# Schematic_EasyEDA.net
KiCad netlist of a schematic drawn in EasyEDA
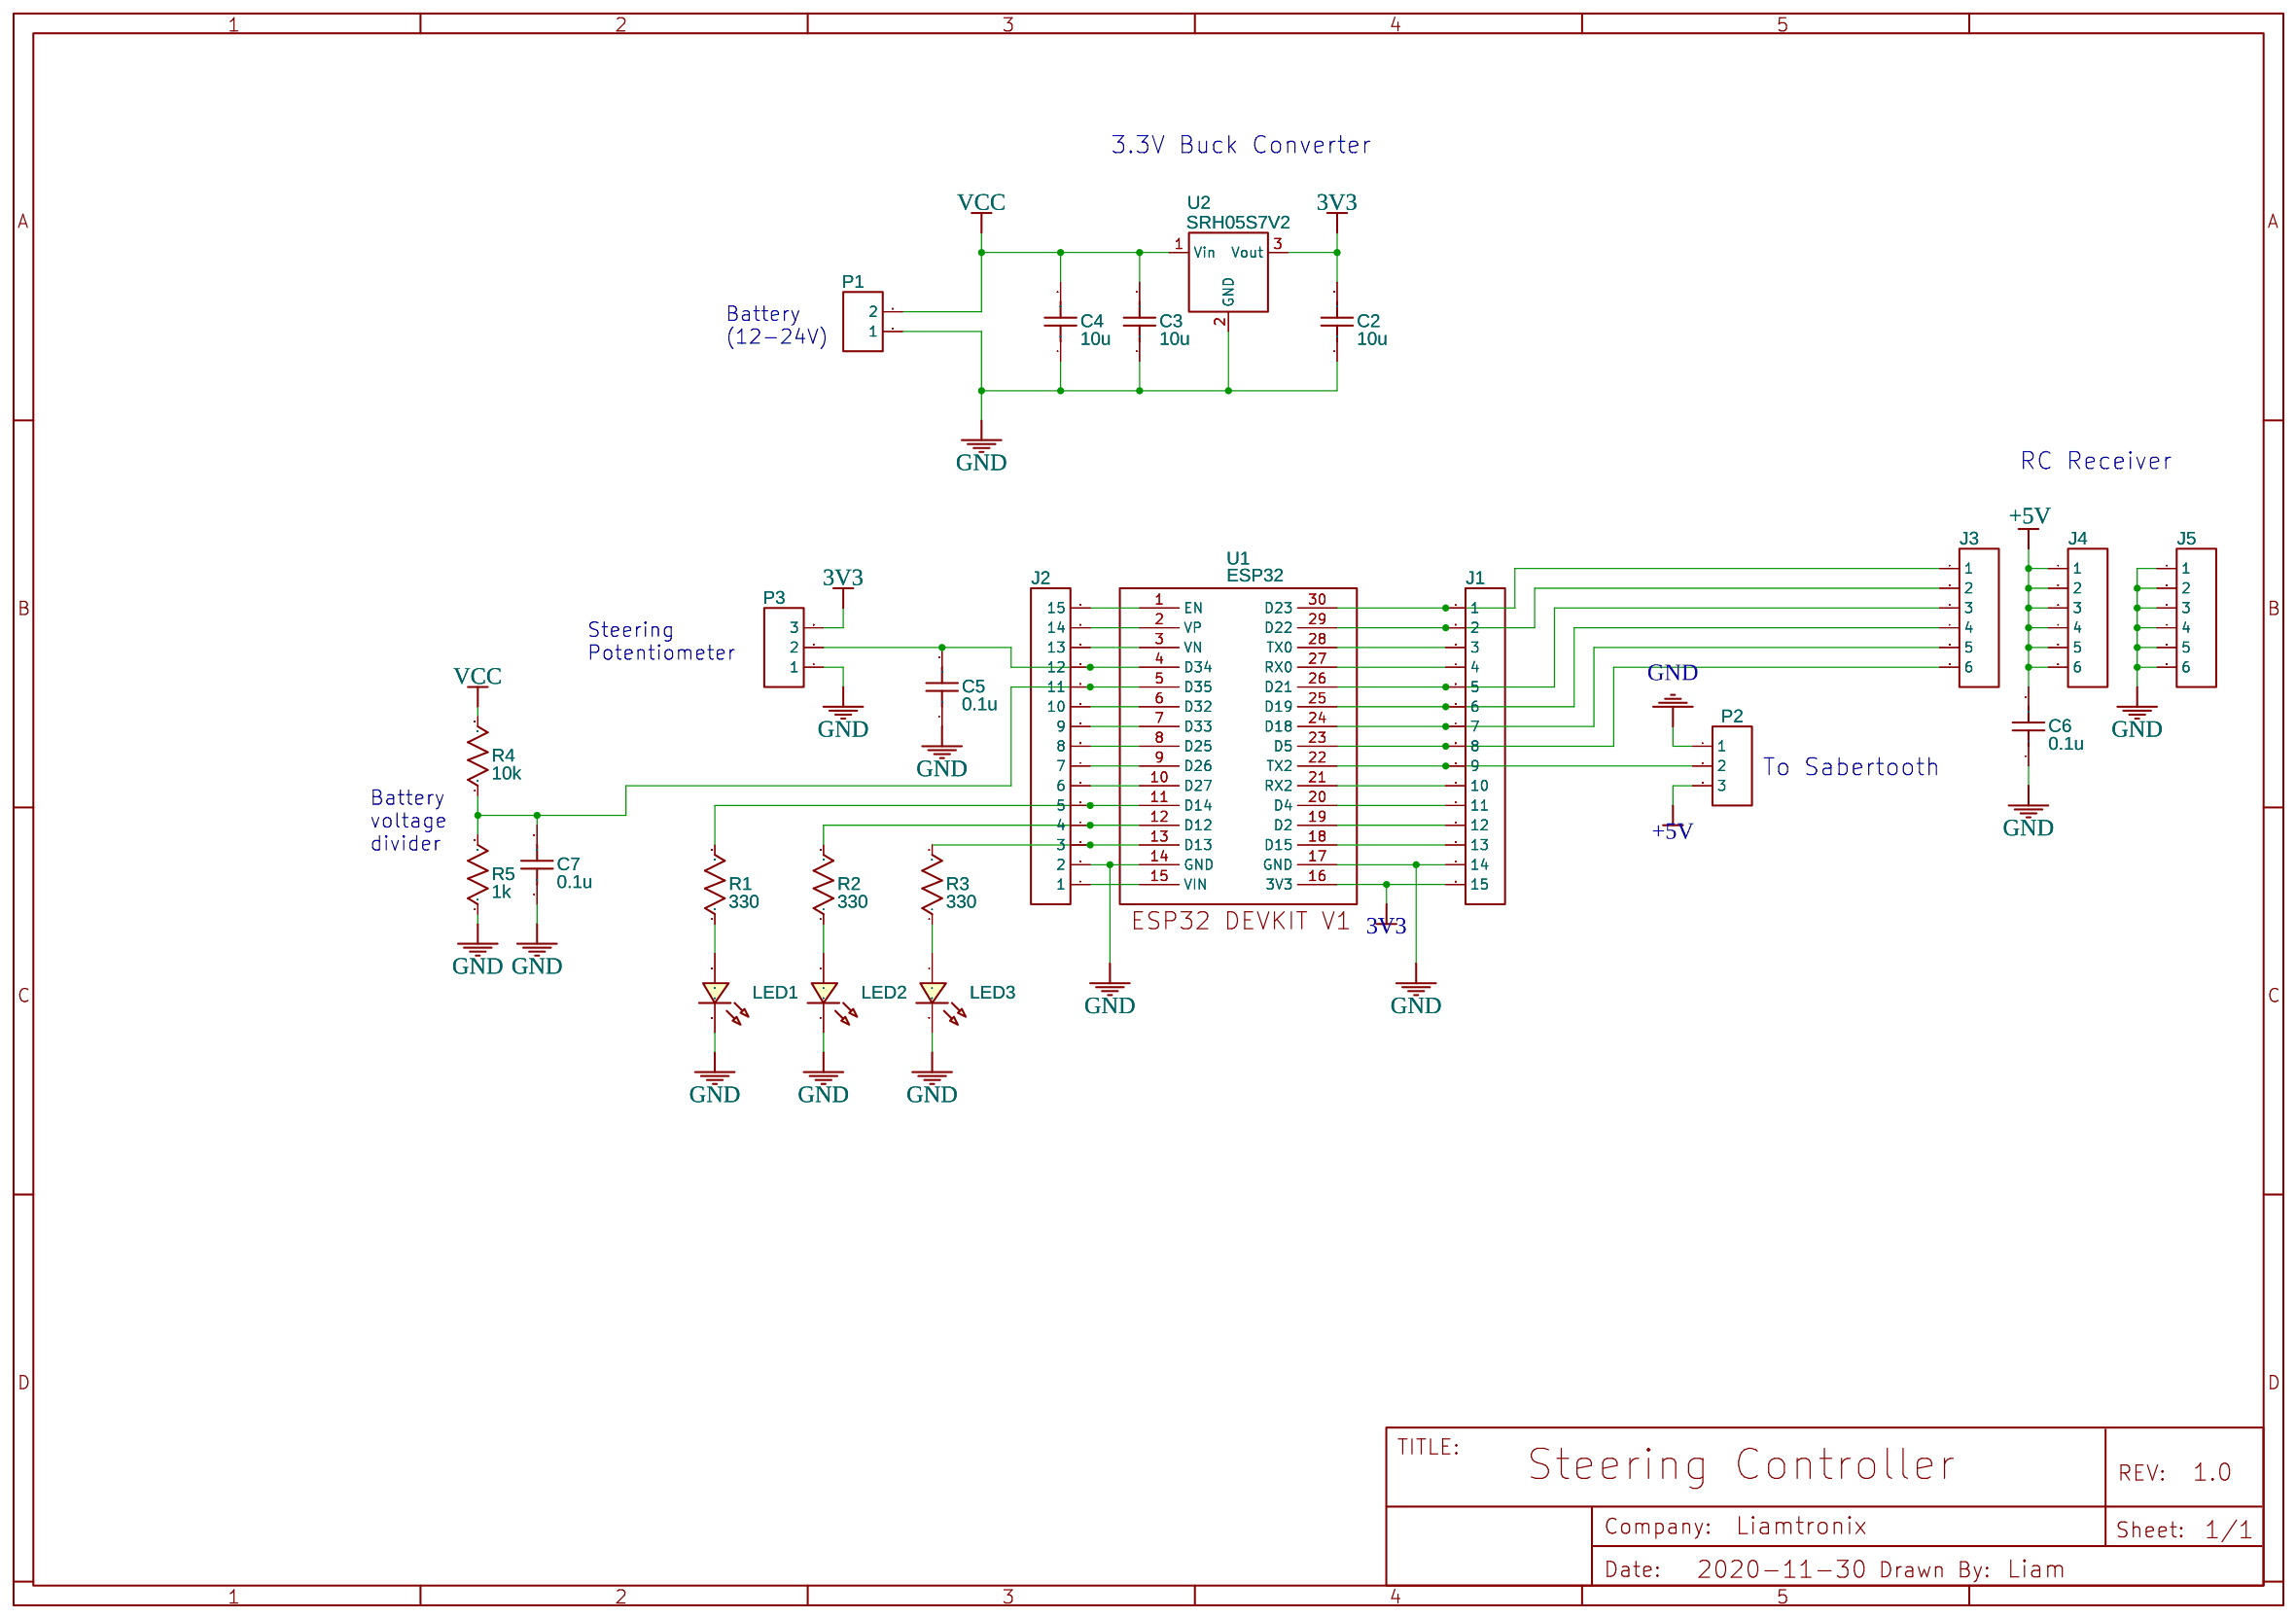
[diagram p0: schematic sheet]

(export (version "E")
  (design (tool "Eeschema 10.0.6"))
  (components
    (comp (ref "C2")
      (value "10u")
      (fields (field (name "BOM_Supplier Part") "1276-6736-1-ND"))
      (libsource (lib "") (part "C_1206_US"))
    )
    (comp (ref "C3")
      (value "10u")
      (fields (field (name "BOM_Supplier Part") "1276-6736-1-ND"))
      (libsource (lib "") (part "C_1206_US"))
    )
    (comp (ref "C4")
      (value "10u")
      (fields (field (name "BOM_Supplier Part") "1276-6736-1-ND"))
      (libsource (lib "") (part "C_1206_US"))
    )
    (comp (ref "C5") (value "0.1u") (libsource (lib "") (part "C_1206_US")))
    (comp (ref "C6") (value "0.1u") (libsource (lib "") (part "C_1206_US")))
    (comp (ref "C7") (value "0.1u") (libsource (lib "") (part "C_1206_US")))
    (comp (ref "J1")
      (value "HDR-M-2.54_1x15")
      (fields (field (name "BOM_Supplier Part") "C124373"))
      (libsource (lib "") (part "HDR-M-2.54_1x15"))
    )
    (comp (ref "J2")
      (value "HDR-M-2.54_1x15")
      (fields (field (name "BOM_Supplier Part") "C124373"))
      (libsource (lib "") (part "HDR-M-2.54_1x15_1"))
    )
    (comp (ref "J3")
      (value "HDR-M-2.54_1x6")
      (fields (field (name "BOM_Supplier Part") "C190819"))
      (libsource (lib "") (part "HDR-M-2.54_1x6"))
    )
    (comp (ref "J4")
      (value "HDR-M-2.54_1x6")
      (fields (field (name "BOM_Supplier Part") "C190819"))
      (libsource (lib "") (part "HDR-M-2.54_1x6"))
    )
    (comp (ref "J5")
      (value "HDR-M-2.54_1x6")
      (fields (field (name "BOM_Supplier Part") "C190819"))
      (libsource (lib "") (part "HDR-M-2.54_1x6"))
    )
    (comp (ref "LED1")
      (value "LED-TH-3mm_R")
      (fields
        (field (name "BOM_Manufacturer Part") "204-10SDRD/S530-A3-L")
        (field (name "BOM_Supplier Part") "C84774")
      )
      (libsource (lib "") (part "LED-TH-3mm_R"))
    )
    (comp (ref "LED2")
      (value "LED-TH-3mm_R")
      (fields
        (field (name "BOM_Manufacturer Part") "204-10SDRD/S530-A3-L")
        (field (name "BOM_Supplier Part") "C84774")
      )
      (libsource (lib "") (part "LED-TH-3mm_R"))
    )
    (comp (ref "LED3")
      (value "LED-TH-3mm_R")
      (fields
        (field (name "BOM_Manufacturer Part") "204-10SDRD/S530-A3-L")
        (field (name "BOM_Supplier Part") "C84774")
      )
      (libsource (lib "") (part "LED-TH-3mm_R"))
    )
    (comp (ref "P1") (value "CONN-TH_2P-P5.00") (libsource (lib "") (part "CONN-TH_2P-P5.00")))
    (comp (ref "P2") (value "CONN-TH_3P-P5.00") (libsource (lib "") (part "CONN-TH_3P-P5.00")))
    (comp (ref "P3") (value "CONN-TH_3P-P5.00") (libsource (lib "") (part "CONN-TH_3P-P5.00_1")))
    (comp (ref "R1") (value "330") (libsource (lib "") (part "R_1206_US")))
    (comp (ref "R2") (value "330") (libsource (lib "") (part "R_1206_US")))
    (comp (ref "R3") (value "330") (libsource (lib "") (part "R_1206_US")))
    (comp (ref "R4") (value "10k") (libsource (lib "") (part "R_1206_US")))
    (comp (ref "R5") (value "1k") (libsource (lib "") (part "R_1206_US")))
    (comp (ref "U1") (value "ESP32") (libsource (lib "") (part "Unknown_570_-505")))
    (comp (ref "U2")
      (value "SRH05S7V2")
      (fields (field (name "BOM_Supplier Part") "174-4675"))
      (libsource (lib "") (part "SRH05S7V2"))
    )
  )
  (nets
    (net (code "1") (name "+5V") (class "Default")
      (node (ref "C6") (pin "2") (pinfunction "2_2") (pintype "unspecified"))
      (node (ref "J4") (pin "1") (pinfunction "1_1") (pintype "input"))
      (node (ref "J4") (pin "2") (pinfunction "2_2") (pintype "input"))
      (node (ref "J4") (pin "3") (pinfunction "3_3") (pintype "input"))
      (node (ref "J4") (pin "4") (pinfunction "4_4") (pintype "input"))
      (node (ref "J4") (pin "5") (pinfunction "5_5") (pintype "input"))
      (node (ref "J4") (pin "6") (pinfunction "6_6") (pintype "input"))
      (node (ref "P2") (pin "3") (pinfunction "3_3") (pintype "unspecified"))
    )
    (net (code "2") (name "3V3") (class "Default")
      (node (ref "C2") (pin "2") (pinfunction "2_2") (pintype "unspecified"))
      (node (ref "J1") (pin "15") (pinfunction "15_15") (pintype "unspecified"))
      (node (ref "P3") (pin "3") (pinfunction "3_3") (pintype "unspecified"))
      (node (ref "U1") (pin "16") (pinfunction "3V3_16") (pintype "unspecified"))
      (node (ref "U2") (pin "3") (pinfunction "Vout_3") (pintype "unspecified"))
    )
    (net (code "3") (name "GND") (class "Default")
      (node (ref "C2") (pin "1") (pinfunction "1_1") (pintype "unspecified"))
      (node (ref "C3") (pin "1") (pinfunction "1_1") (pintype "unspecified"))
      (node (ref "C4") (pin "1") (pinfunction "1_1") (pintype "unspecified"))
      (node (ref "C5") (pin "1") (pinfunction "1_1") (pintype "unspecified"))
      (node (ref "C6") (pin "1") (pinfunction "1_1") (pintype "unspecified"))
      (node (ref "C7") (pin "1") (pinfunction "1_1") (pintype "unspecified"))
      (node (ref "J1") (pin "14") (pinfunction "14_14") (pintype "unspecified"))
      (node (ref "J2") (pin "2") (pinfunction "2_2") (pintype "unspecified"))
      (node (ref "J5") (pin "1") (pinfunction "1_1") (pintype "input"))
      (node (ref "J5") (pin "2") (pinfunction "2_2") (pintype "input"))
      (node (ref "J5") (pin "3") (pinfunction "3_3") (pintype "input"))
      (node (ref "J5") (pin "4") (pinfunction "4_4") (pintype "input"))
      (node (ref "J5") (pin "5") (pinfunction "5_5") (pintype "input"))
      (node (ref "J5") (pin "6") (pinfunction "6_6") (pintype "input"))
      (node (ref "LED1") (pin "2") (pinfunction "2_2") (pintype "unspecified"))
      (node (ref "LED2") (pin "2") (pinfunction "2_2") (pintype "unspecified"))
      (node (ref "LED3") (pin "2") (pinfunction "2_2") (pintype "unspecified"))
      (node (ref "P1") (pin "1") (pinfunction "1_1") (pintype "unspecified"))
      (node (ref "P2") (pin "1") (pinfunction "1_1") (pintype "unspecified"))
      (node (ref "P3") (pin "1") (pinfunction "1_1") (pintype "unspecified"))
      (node (ref "R5") (pin "1") (pinfunction "1_1") (pintype "unspecified"))
      (node (ref "U1") (pin "14") (pinfunction "GND_14") (pintype "unspecified"))
      (node (ref "U1") (pin "17") (pinfunction "GND_17") (pintype "unspecified"))
      (node (ref "U2") (pin "2") (pinfunction "GND_2") (pintype "unspecified"))
    )
    (net (code "4") (name "Net-(LED1-Pad1)") (class "Default")
      (node (ref "LED1") (pin "1") (pinfunction "1_1") (pintype "unspecified"))
      (node (ref "R1") (pin "1") (pinfunction "1_1") (pintype "unspecified"))
    )
    (net (code "5") (name "Net-(LED2-Pad1)") (class "Default")
      (node (ref "LED2") (pin "1") (pinfunction "1_1") (pintype "unspecified"))
      (node (ref "R2") (pin "1") (pinfunction "1_1") (pintype "unspecified"))
    )
    (net (code "6") (name "Net-(LED3-Pad1)") (class "Default")
      (node (ref "LED3") (pin "1") (pinfunction "1_1") (pintype "unspecified"))
      (node (ref "R3") (pin "1") (pinfunction "1_1") (pintype "unspecified"))
    )
    (net (code "7") (name "Net-(U1-D2)") (class "Default")
      (node (ref "J1") (pin "12") (pinfunction "12_12") (pintype "unspecified"))
      (node (ref "U1") (pin "19") (pinfunction "D2_19") (pintype "unspecified"))
    )
    (net (code "8") (name "Net-(U1-D4)") (class "Default")
      (node (ref "J1") (pin "11") (pinfunction "11_11") (pintype "unspecified"))
      (node (ref "U1") (pin "20") (pinfunction "D4_20") (pintype "unspecified"))
    )
    (net (code "9") (name "Net-(U1-D5)") (class "Default")
      (node (ref "J1") (pin "8") (pinfunction "8_8") (pintype "unspecified"))
      (node (ref "J3") (pin "6") (pinfunction "6_6") (pintype "input"))
      (node (ref "U1") (pin "23") (pinfunction "D5_23") (pintype "unspecified"))
    )
    (net (code "10") (name "Net-(U1-D12)") (class "Default")
      (node (ref "J2") (pin "4") (pinfunction "4_4") (pintype "unspecified"))
      (node (ref "R2") (pin "2") (pinfunction "2_2") (pintype "unspecified"))
      (node (ref "U1") (pin "12") (pinfunction "D12_12") (pintype "unspecified"))
    )
    (net (code "11") (name "Net-(U1-D13)") (class "Default")
      (node (ref "J2") (pin "3") (pinfunction "3_3") (pintype "unspecified"))
      (node (ref "R3") (pin "2") (pinfunction "2_2") (pintype "unspecified"))
      (node (ref "U1") (pin "13") (pinfunction "D13_13") (pintype "unspecified"))
    )
    (net (code "12") (name "Net-(U1-D14)") (class "Default")
      (node (ref "J2") (pin "5") (pinfunction "5_5") (pintype "unspecified"))
      (node (ref "R1") (pin "2") (pinfunction "2_2") (pintype "unspecified"))
      (node (ref "U1") (pin "11") (pinfunction "D14_11") (pintype "unspecified"))
    )
    (net (code "13") (name "Net-(U1-D15)") (class "Default")
      (node (ref "J1") (pin "13") (pinfunction "13_13") (pintype "unspecified"))
      (node (ref "U1") (pin "18") (pinfunction "D15_18") (pintype "unspecified"))
    )
    (net (code "14") (name "Net-(U1-D18)") (class "Default")
      (node (ref "J1") (pin "7") (pinfunction "7_7") (pintype "unspecified"))
      (node (ref "J3") (pin "5") (pinfunction "5_5") (pintype "input"))
      (node (ref "U1") (pin "24") (pinfunction "D18_24") (pintype "unspecified"))
    )
    (net (code "15") (name "Net-(U1-D19)") (class "Default")
      (node (ref "J1") (pin "6") (pinfunction "6_6") (pintype "unspecified"))
      (node (ref "J3") (pin "4") (pinfunction "4_4") (pintype "input"))
      (node (ref "U1") (pin "25") (pinfunction "D19_25") (pintype "unspecified"))
    )
    (net (code "16") (name "Net-(U1-D21)") (class "Default")
      (node (ref "J1") (pin "5") (pinfunction "5_5") (pintype "unspecified"))
      (node (ref "J3") (pin "3") (pinfunction "3_3") (pintype "input"))
      (node (ref "U1") (pin "26") (pinfunction "D21_26") (pintype "unspecified"))
    )
    (net (code "17") (name "Net-(U1-D22)") (class "Default")
      (node (ref "J1") (pin "2") (pinfunction "2_2") (pintype "unspecified"))
      (node (ref "J3") (pin "2") (pinfunction "2_2") (pintype "input"))
      (node (ref "U1") (pin "29") (pinfunction "D22_29") (pintype "unspecified"))
    )
    (net (code "18") (name "Net-(U1-D23)") (class "Default")
      (node (ref "J1") (pin "1") (pinfunction "1_1") (pintype "unspecified"))
      (node (ref "J3") (pin "1") (pinfunction "1_1") (pintype "input"))
      (node (ref "U1") (pin "30") (pinfunction "D23_30") (pintype "unspecified"))
    )
    (net (code "19") (name "Net-(U1-D25)") (class "Default")
      (node (ref "J2") (pin "8") (pinfunction "8_8") (pintype "unspecified"))
      (node (ref "U1") (pin "8") (pinfunction "D25_8") (pintype "unspecified"))
    )
    (net (code "20") (name "Net-(U1-D26)") (class "Default")
      (node (ref "J2") (pin "7") (pinfunction "7_7") (pintype "unspecified"))
      (node (ref "U1") (pin "9") (pinfunction "D26_9") (pintype "unspecified"))
    )
    (net (code "21") (name "Net-(U1-D27)") (class "Default")
      (node (ref "J2") (pin "6") (pinfunction "6_6") (pintype "unspecified"))
      (node (ref "U1") (pin "10") (pinfunction "D27_10") (pintype "unspecified"))
    )
    (net (code "22") (name "Net-(U1-D32)") (class "Default")
      (node (ref "J2") (pin "10") (pinfunction "10_10") (pintype "unspecified"))
      (node (ref "U1") (pin "6") (pinfunction "D32_6") (pintype "unspecified"))
    )
    (net (code "23") (name "Net-(U1-D33)") (class "Default")
      (node (ref "J2") (pin "9") (pinfunction "9_9") (pintype "unspecified"))
      (node (ref "U1") (pin "7") (pinfunction "D33_7") (pintype "unspecified"))
    )
    (net (code "24") (name "Net-(U1-D34)") (class "Default")
      (node (ref "C5") (pin "2") (pinfunction "2_2") (pintype "unspecified"))
      (node (ref "J2") (pin "12") (pinfunction "12_12") (pintype "unspecified"))
      (node (ref "P3") (pin "2") (pinfunction "2_2") (pintype "unspecified"))
      (node (ref "U1") (pin "4") (pinfunction "D34_4") (pintype "unspecified"))
    )
    (net (code "25") (name "Net-(U1-D35)") (class "Default")
      (node (ref "C7") (pin "2") (pinfunction "2_2") (pintype "unspecified"))
      (node (ref "J2") (pin "11") (pinfunction "11_11") (pintype "unspecified"))
      (node (ref "R4") (pin "1") (pinfunction "1_1") (pintype "unspecified"))
      (node (ref "R5") (pin "2") (pinfunction "2_2") (pintype "unspecified"))
      (node (ref "U1") (pin "5") (pinfunction "D35_5") (pintype "unspecified"))
    )
    (net (code "26") (name "Net-(U1-EN)") (class "Default")
      (node (ref "J2") (pin "15") (pinfunction "15_15") (pintype "unspecified"))
      (node (ref "U1") (pin "1") (pinfunction "EN_1") (pintype "unspecified"))
    )
    (net (code "27") (name "Net-(U1-RX0)") (class "Default")
      (node (ref "J1") (pin "4") (pinfunction "4_4") (pintype "unspecified"))
      (node (ref "U1") (pin "27") (pinfunction "RX0_27") (pintype "unspecified"))
    )
    (net (code "28") (name "Net-(U1-RX2)") (class "Default")
      (node (ref "J1") (pin "10") (pinfunction "10_10") (pintype "unspecified"))
      (node (ref "U1") (pin "21") (pinfunction "RX2_21") (pintype "unspecified"))
    )
    (net (code "29") (name "Net-(U1-TX0)") (class "Default")
      (node (ref "J1") (pin "3") (pinfunction "3_3") (pintype "unspecified"))
      (node (ref "U1") (pin "28") (pinfunction "TX0_28") (pintype "unspecified"))
    )
    (net (code "30") (name "Net-(U1-TX2)") (class "Default")
      (node (ref "J1") (pin "9") (pinfunction "9_9") (pintype "unspecified"))
      (node (ref "P2") (pin "2") (pinfunction "2_2") (pintype "unspecified"))
      (node (ref "U1") (pin "22") (pinfunction "TX2_22") (pintype "unspecified"))
    )
    (net (code "31") (name "Net-(U1-VIN)") (class "Default")
      (node (ref "J2") (pin "1") (pinfunction "1_1") (pintype "unspecified"))
      (node (ref "U1") (pin "15") (pinfunction "VIN_15") (pintype "unspecified"))
    )
    (net (code "32") (name "Net-(U1-VN)") (class "Default")
      (node (ref "J2") (pin "13") (pinfunction "13_13") (pintype "unspecified"))
      (node (ref "U1") (pin "3") (pinfunction "VN_3") (pintype "unspecified"))
    )
    (net (code "33") (name "Net-(U1-VP)") (class "Default")
      (node (ref "J2") (pin "14") (pinfunction "14_14") (pintype "unspecified"))
      (node (ref "U1") (pin "2") (pinfunction "VP_2") (pintype "unspecified"))
    )
    (net (code "34") (name "VCC") (class "Default")
      (node (ref "C3") (pin "2") (pinfunction "2_2") (pintype "unspecified"))
      (node (ref "C4") (pin "2") (pinfunction "2_2") (pintype "unspecified"))
      (node (ref "P1") (pin "2") (pinfunction "2_2") (pintype "unspecified"))
      (node (ref "R4") (pin "2") (pinfunction "2_2") (pintype "unspecified"))
      (node (ref "U2") (pin "1") (pinfunction "Vin_1") (pintype "unspecified"))
    )
  )
)
